# LedBoard.net
KiCad netlist of a schematic drawn in Altium Designer
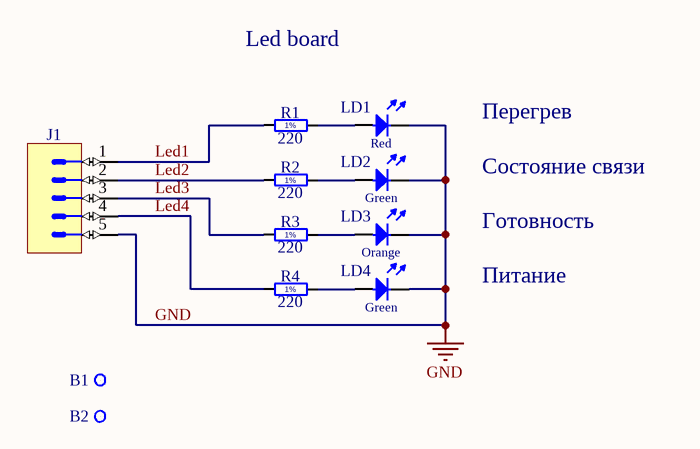
[diagram p0: LedBoard.SchDoc]

(export (version "E")
  (design (tool "Eeschema 10.0.6"))
  (components
    (comp (ref "B1")
      (value "Non Plated Hole")
      (footprint "MTG300")
      (description "Single Terminal Socket")
      (fields (field (name "PART NUMBER") "NON-PLATED_HOLE3.0") (field (name "AUTHOR") "CERN DEM JLC"))
      (libsource (lib "Eletro-mechanical") (part "Single Terminal Socket"))
    )
    (comp (ref "B2")
      (value "Non Plated Hole")
      (footprint "MTG300")
      (description "Single Terminal Socket")
      (fields (field (name "PART NUMBER") "NON-PLATED_HOLE3.0") (field (name "AUTHOR") "CERN DEM JLC"))
      (libsource (lib "Eletro-mechanical") (part "Single Terminal Socket"))
    )
    (comp (ref "J1")
      (value "KK®")
      (footprint "MOLEX_22-27-2051")
      (description "Connector 5 Male")
      (fields
        (field (name "PART NUMBER") "MOLEX_22-27-2051")
        (field (name "MANUFACTURER") "MOLEX")
        (field (name "AUTHOR") "CERN DEM JLC")
      )
      (libsource (lib "Connectors") (part "Connector 5 Male"))
    )
    (comp (ref "LD1")
      (value "Super Red")
      (footprint "LED_OSRAM_LSR976")
      (description "LED Red 1C 2A")
      (fields
        (field (name "PART NUMBER") "LED_OSRAM_LSR976")
        (field (name "MANUFACTURER") "OSRAM")
        (field (name "AUTHOR") "CERN DEM JLC")
      )
      (libsource (lib "ICs And Semiconductors") (part "LED Red 1C 2A"))
    )
    (comp (ref "LD2")
      (value "Green")
      (footprint "LED_OSRAM_LGR971")
      (description "LED Green 1C 2A")
      (fields
        (field (name "PART NUMBER") "LED_OSRAM_LGR971")
        (field (name "MANUFACTURER") "OSRAM")
        (field (name "AUTHOR") "CERN DEM JLC")
      )
      (libsource (lib "ICs And Semiconductors") (part "LED Green 1C 2A"))
    )
    (comp (ref "LD3")
      (value "Orange")
      (footprint "LED_OSRAM_LOR976")
      (description "LED Orange 1C 2A")
      (fields
        (field (name "PART NUMBER") "LED_OSRAM_LOR976")
        (field (name "MANUFACTURER") "OSRAM")
        (field (name "AUTHOR") "CERN DEM JLC")
      )
      (libsource (lib "ICs And Semiconductors") (part "LED Orange 1C 2A"))
    )
    (comp (ref "LD4")
      (value "Green")
      (footprint "LED_OSRAM_LGR971")
      (description "LED Green 1C 2A")
      (fields
        (field (name "PART NUMBER") "LED_OSRAM_LGR971")
        (field (name "MANUFACTURER") "OSRAM")
        (field (name "AUTHOR") "CERN DEM JLC")
      )
      (libsource (lib "ICs And Semiconductors") (part "LED Green 1C 2A"))
    )
    (comp (ref "R1")
      (value "220")
      (footprint "RESC2012X60N")
      (description "Resistor - 1%")
      (fields
        (field (name "PART NUMBER") "R0805_220R_1%_0.125W_100PPM")
        (field (name "POWER") "0.125W")
        (field (name "AUTHOR") "CERN DEM JLC")
      )
      (libsource (lib "Resistors") (part "Resistor - 1%"))
    )
    (comp (ref "R2")
      (value "220")
      (footprint "RESC2012X60N")
      (description "Resistor - 1%")
      (fields
        (field (name "PART NUMBER") "R0805_220R_1%_0.125W_100PPM")
        (field (name "POWER") "0.125W")
        (field (name "AUTHOR") "CERN DEM JLC")
      )
      (libsource (lib "Resistors") (part "Resistor - 1%"))
    )
    (comp (ref "R3")
      (value "220")
      (footprint "RESC2012X60N")
      (description "Resistor - 1%")
      (fields
        (field (name "PART NUMBER") "R0805_220R_1%_0.125W_100PPM")
        (field (name "POWER") "0.125W")
        (field (name "AUTHOR") "CERN DEM JLC")
      )
      (libsource (lib "Resistors") (part "Resistor - 1%"))
    )
    (comp (ref "R4")
      (value "220")
      (footprint "RESC2012X60N")
      (description "Resistor - 1%")
      (fields
        (field (name "PART NUMBER") "R0805_220R_1%_0.125W_100PPM")
        (field (name "POWER") "0.125W")
        (field (name "AUTHOR") "CERN DEM JLC")
      )
      (libsource (lib "Resistors") (part "Resistor - 1%"))
    )
  )
  (nets
    (net (code "1") (name "/Led1") (class "Default")
      (node (ref "J1") (pin "1") (pinfunction "1_1") (pintype "bidirectional"))
      (node (ref "R1") (pin "1") (pinfunction "1_1") (pintype "passive"))
    )
    (net (code "2") (name "/Led2") (class "Default")
      (node (ref "J1") (pin "2") (pinfunction "2_2") (pintype "bidirectional"))
      (node (ref "R2") (pin "1") (pinfunction "1_1") (pintype "passive"))
    )
    (net (code "3") (name "/Led3") (class "Default")
      (node (ref "J1") (pin "3") (pinfunction "3_3") (pintype "bidirectional"))
      (node (ref "R3") (pin "1") (pinfunction "1_1") (pintype "passive"))
    )
    (net (code "4") (name "/Led4") (class "Default")
      (node (ref "J1") (pin "4") (pinfunction "4_4") (pintype "bidirectional"))
      (node (ref "R4") (pin "1") (pinfunction "1_1") (pintype "passive"))
    )
    (net (code "5") (name "GND") (class "Default")
      (node (ref "J1") (pin "5") (pinfunction "5_5") (pintype "bidirectional"))
      (node (ref "LD1") (pin "1") (pinfunction "C_1") (pintype "passive"))
      (node (ref "LD2") (pin "1") (pinfunction "C_1") (pintype "passive"))
      (node (ref "LD3") (pin "1") (pinfunction "C_1") (pintype "passive"))
      (node (ref "LD4") (pin "1") (pinfunction "C_1") (pintype "passive"))
    )
    (net (code "6") (name "Net-(LD1-A)") (class "Default")
      (node (ref "LD1") (pin "2") (pinfunction "A_2") (pintype "passive"))
      (node (ref "R1") (pin "2") (pinfunction "2_2") (pintype "passive"))
    )
    (net (code "7") (name "Net-(LD2-A)") (class "Default")
      (node (ref "LD2") (pin "2") (pinfunction "A_2") (pintype "passive"))
      (node (ref "R2") (pin "2") (pinfunction "2_2") (pintype "passive"))
    )
    (net (code "8") (name "Net-(LD3-A)") (class "Default")
      (node (ref "LD3") (pin "2") (pinfunction "A_2") (pintype "passive"))
      (node (ref "R3") (pin "2") (pinfunction "2_2") (pintype "passive"))
    )
    (net (code "9") (name "Net-(LD4-A)") (class "Default")
      (node (ref "LD4") (pin "2") (pinfunction "A_2") (pintype "passive"))
      (node (ref "R4") (pin "2") (pinfunction "2_2") (pintype "passive"))
    )
    (net (code "10") (name "unconnected-(B1-Pad1)") (class "Default")
      (node (ref "B1") (pin "1") (pinfunction "1_1") (pintype "bidirectional"))
    )
    (net (code "11") (name "unconnected-(B2-Pad1)") (class "Default")
      (node (ref "B2") (pin "1") (pinfunction "1_1") (pintype "bidirectional"))
    )
  )
)
